# Sheet1.net
KiCad netlist of a schematic drawn in Altium Designer
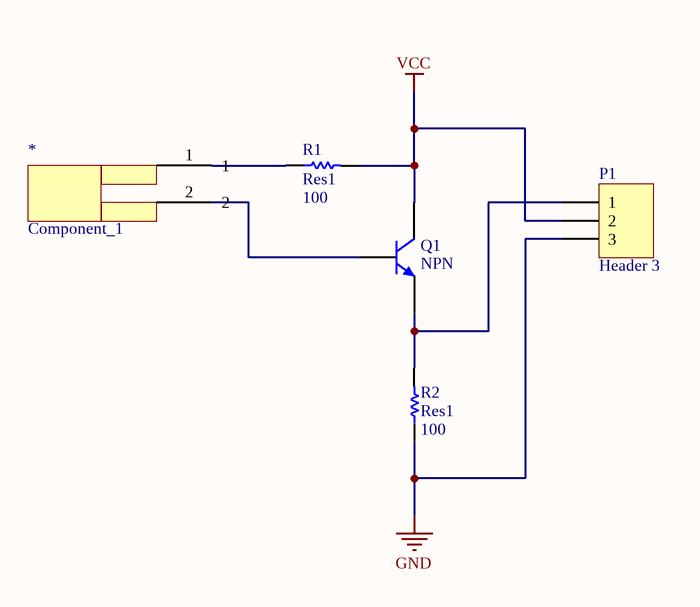
[diagram p0: Sheet1.SchDoc]

(export (version "E")
  (design (tool "Eeschema 10.0.6"))
  (components
    (comp (ref "*")
      (value "Component_1")
      (footprint "zhangchong:LED")
      (libsource (lib "Schlib1") (part "Component_1"))
    )
    (comp (ref "P1")
      (value "Header 3")
      (footprint "传感器:sh-2.0")
      (description "Header, 3-Pin")
      (fields (field (name "PUBLISHER") "Altium Limited"))
      (libsource (lib "Miscellaneous Connectors") (part "Header 3"))
    )
    (comp (ref "Q1")
      (value "NPN")
      (footprint "Miscellaneous Devices:SOT23_M")
      (description "NPN Bipolar Transistor")
      (fields (field (name "PUBLISHER") "Altium Limited"))
      (libsource (lib "Miscellaneous Devices") (part "NPN"))
    )
    (comp (ref "R1")
      (value "Res1")
      (footprint "Miscellaneous Devices:1608[0603]")
      (description "Resistor")
      (fields (field (name "ALTIUM_VALUE") "100") (field (name "PUBLISHER") "Altium Limited"))
      (libsource (lib "Miscellaneous Devices") (part "Res1"))
    )
    (comp (ref "R2")
      (value "Res1")
      (footprint "Miscellaneous Devices:1608[0603]")
      (description "Resistor")
      (fields (field (name "ALTIUM_VALUE") "100") (field (name "PUBLISHER") "Altium Limited"))
      (libsource (lib "Miscellaneous Devices") (part "Res1"))
    )
  )
  (nets
    (net (code "1") (name "GND") (class "Default")
      (node (ref "P1") (pin "3") (pinfunction "3_3") (pintype "passive"))
      (node (ref "R2") (pin "1") (pinfunction "1_1") (pintype "passive"))
    )
    (net (code "2") (name "Net-(Q1-E)") (class "Default")
      (node (ref "P1") (pin "1") (pinfunction "1_1") (pintype "passive"))
      (node (ref "Q1") (pin "3") (pinfunction "E_3") (pintype "passive"))
      (node (ref "R2") (pin "2") (pinfunction "2_2") (pintype "passive"))
    )
    (net (code "3") (name "VCC") (class "Default")
      (node (ref "P1") (pin "2") (pinfunction "2_2") (pintype "passive"))
      (node (ref "Q1") (pin "1") (pinfunction "C_1") (pintype "passive"))
      (node (ref "R1") (pin "2") (pinfunction "2_2") (pintype "passive"))
    )
    (net (code "4") (name "unconnected-(*-Pad1)") (class "Default")
      (node (ref "*") (pin "1") (pinfunction "1_1") (pintype "passive"))
    )
    (net (code "5") (name "unconnected-(*-Pad2)") (class "Default")
      (node (ref "*") (pin "2") (pinfunction "2_2") (pintype "passive"))
    )
    (net (code "6") (name "unconnected-(Q1-B-Pad2)") (class "Default")
      (node (ref "Q1") (pin "2") (pinfunction "B_2") (pintype "passive"))
    )
    (net (code "7") (name "unconnected-(R1-Pad1)") (class "Default")
      (node (ref "R1") (pin "1") (pinfunction "1_1") (pintype "passive"))
    )
  )
)
